# battery_monitor_6803-2_Rev5.net
KiCad netlist of a schematic drawn in EAGLE
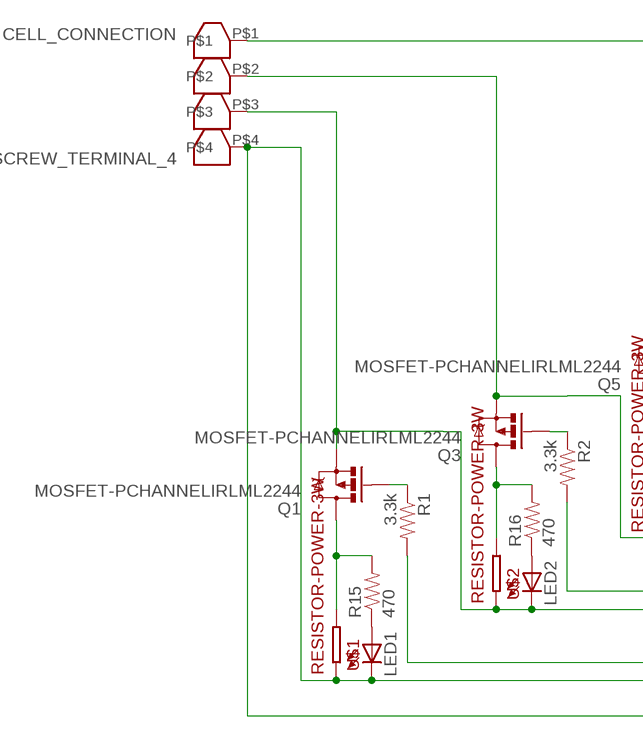
[diagram p0: schematic, sheet 1, part 1 of 2]
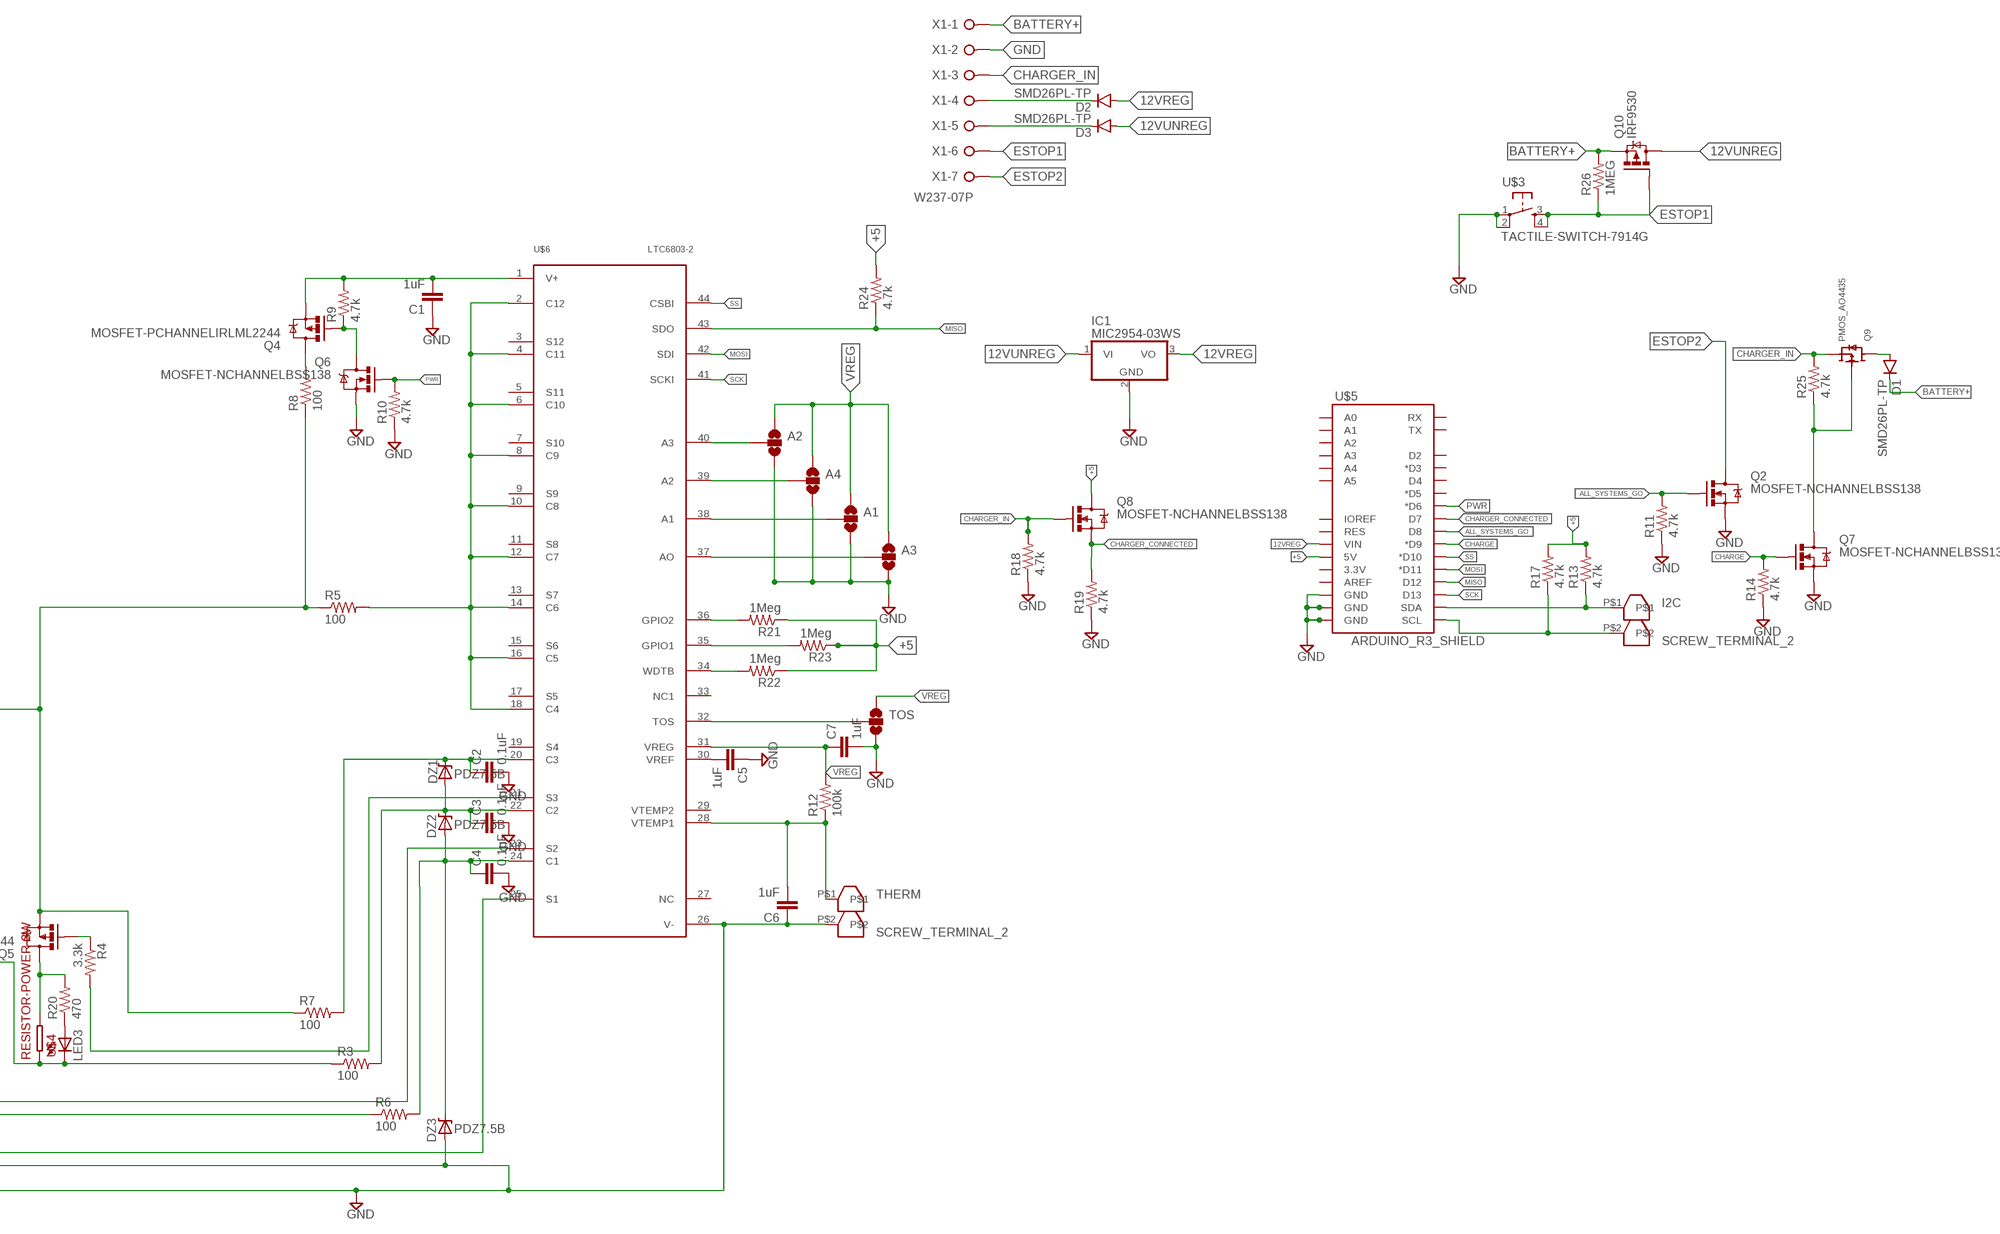
[diagram p1: schematic, sheet 1, part 2 of 2]

(export (version "E")
  (design (tool "Eeschema 10.0.6"))
  (components
    (comp (ref "A1")
      (value "SOLDERJUMPER_2WAYS")
      (footprint "eagle-import:SJ_3")
      (libsource (lib "eagle-import") (part "SOLDERJUMPER_2WAYS"))
    )
    (comp (ref "A2")
      (value "SOLDERJUMPER_2WAYS")
      (footprint "eagle-import:SJ_3")
      (libsource (lib "eagle-import") (part "SOLDERJUMPER_2WAYS"))
    )
    (comp (ref "A3")
      (value "SOLDERJUMPER_2WAYS")
      (footprint "eagle-import:SJ_3")
      (libsource (lib "eagle-import") (part "SOLDERJUMPER_2WAYS"))
    )
    (comp (ref "A4")
      (value "SOLDERJUMPER_2WAYS")
      (footprint "eagle-import:SJ_3")
      (libsource (lib "eagle-import") (part "SOLDERJUMPER_2WAYS"))
    )
    (comp (ref "C1")
      (value "1uF")
      (footprint "eagle-import:0603-CAP")
      (fields (field (name "MPN") "C0603X5R0J105M030BC") (field (name "PROD_ID") "CAP-08390"))
      (libsource (lib "eagle-import") (part "0.1UF-100V-10%(0603)"))
    )
    (comp (ref "C2")
      (value "0.1uF")
      (footprint "eagle-import:0603-CAP")
      (fields (field (name "MF") "AVX CORPORATION") (field (name "MPN") "0603YG104ZAT2A"))
      (libsource (lib "eagle-import") (part "0.1UF-100V-10%(0603)"))
    )
    (comp (ref "C3")
      (value "0.1uF")
      (footprint "eagle-import:0603-CAP")
      (fields (field (name "MF") "AVX CORPORATION") (field (name "MPN") "0603YG104ZAT2A"))
      (libsource (lib "eagle-import") (part "0.1UF-100V-10%(0603)"))
    )
    (comp (ref "C4")
      (value "0.1uF")
      (footprint "eagle-import:0603-CAP")
      (fields (field (name "MF") "AVX CORPORATION") (field (name "MPN") "0603YG104ZAT2A"))
      (libsource (lib "eagle-import") (part "0.1UF-100V-10%(0603)"))
    )
    (comp (ref "C5")
      (value "1uF")
      (footprint "eagle-import:0603-CAP")
      (fields (field (name "MPN") "C0603X5R0J105M030BC") (field (name "PROD_ID") "CAP-08390"))
      (libsource (lib "eagle-import") (part "0.1UF-100V-10%(0603)"))
    )
    (comp (ref "C6")
      (value "1uF")
      (footprint "eagle-import:0603-CAP")
      (fields (field (name "MPN") "C0603X5R0J105M030BC") (field (name "PROD_ID") "CAP-08390"))
      (libsource (lib "eagle-import") (part "0.1UF-100V-10%(0603)"))
    )
    (comp (ref "C7")
      (value "1uF")
      (footprint "eagle-import:0603-CAP")
      (fields (field (name "MPN") "C0603X5R0J105M030BC") (field (name "PROD_ID") "CAP-08390"))
      (libsource (lib "eagle-import") (part "0.1UF-100V-10%(0603)"))
    )
    (comp (ref "CELL_CONNECTION")
      (value "SCREW_TERMINAL_4")
      (footprint "eagle-import:SCREW_TERMINAL_4")
      (fields (field (name "MF") "TYCO ELECTRONICS") (field (name "MPN") "282834-4"))
      (libsource (lib "eagle-import") (part "SCREW_TERMINAL_4"))
    )
    (comp (ref "D1")
      (value "SMD26PL-TP")
      (footprint "eagle-import:SOD-123")
      (libsource (lib "eagle-import") (part "DIODESOD123"))
    )
    (comp (ref "D2")
      (value "SMD26PL-TP")
      (footprint "eagle-import:SOD-123")
      (libsource (lib "eagle-import") (part "DIODESOD123"))
    )
    (comp (ref "D3")
      (value "SMD26PL-TP")
      (footprint "eagle-import:SOD-123")
      (libsource (lib "eagle-import") (part "DIODESOD123"))
    )
    (comp (ref "DZ1")
      (value "PDZ7.5B")
      (footprint "eagle-import:SOD-323@1")
      (fields (field (name "MPN") "PDZ7.5B,115"))
      (libsource (lib "eagle-import") (part "DIODE-ZENER-BZT52"))
    )
    (comp (ref "DZ2")
      (value "PDZ7.5B")
      (footprint "eagle-import:SOD-323@1")
      (fields (field (name "MPN") "PDZ7.5B,115"))
      (libsource (lib "eagle-import") (part "DIODE-ZENER-BZT52"))
    )
    (comp (ref "DZ3")
      (value "PDZ7.5B")
      (footprint "eagle-import:SOD-323@1")
      (fields (field (name "MPN") "PDZ7.5B,115"))
      (libsource (lib "eagle-import") (part "DIODE-ZENER-BZT52"))
    )
    (comp (ref "I2C")
      (value "SCREW_TERMINAL_2")
      (footprint "eagle-import:SCREW_TERMINAL_2")
      (fields (field (name "MF") "TYCO ELECTRONICS") (field (name "MPN") "282834-2"))
      (libsource (lib "eagle-import") (part "SCREW_TERMINAL_2"))
    )
    (comp (ref "IC1")
      (value "MIC2954-03WS")
      (footprint "eagle-import:SOT223")
      (libsource (lib "eagle-import") (part "MCP1703DB"))
    )
    (comp (ref "LED1")
      (value "LED0603")
      (footprint "eagle-import:LED-0603")
      (fields (field (name "MPN") "150060RS75000"))
      (libsource (lib "eagle-import") (part "LED0603"))
    )
    (comp (ref "LED2")
      (value "LED0603")
      (footprint "eagle-import:LED-0603")
      (fields (field (name "MPN") "150060RS75000"))
      (libsource (lib "eagle-import") (part "LED0603"))
    )
    (comp (ref "LED3")
      (value "LED0603")
      (footprint "eagle-import:LED-0603")
      (fields (field (name "MPN") "150060RS75000"))
      (libsource (lib "eagle-import") (part "LED0603"))
    )
    (comp (ref "Q1")
      (value "MOSFET-PCHANNELIRLML2244")
      (footprint "eagle-import:SOT23-3@1")
      (fields (field (name "MPN") "SI2369DS-T1-GE3"))
      (libsource (lib "eagle-import") (part "MOSFET-PCHANNELIRLML2244"))
    )
    (comp (ref "Q2")
      (value "MOSFET-NCHANNELBSS138")
      (footprint "eagle-import:SOT23")
      (fields (field (name "MPN") "IRLML0030TRPBF"))
      (libsource (lib "eagle-import") (part "MOSFET-NCHANNELBSS138"))
    )
    (comp (ref "Q3")
      (value "MOSFET-PCHANNELIRLML2244")
      (footprint "eagle-import:SOT23-3@1")
      (fields (field (name "MPN") "SI2369DS-T1-GE3"))
      (libsource (lib "eagle-import") (part "MOSFET-PCHANNELIRLML2244"))
    )
    (comp (ref "Q4")
      (value "MOSFET-PCHANNELIRLML2244")
      (footprint "eagle-import:SOT23-3@1")
      (fields (field (name "MPN") "SI2369DS-T1-GE3"))
      (libsource (lib "eagle-import") (part "MOSFET-PCHANNELIRLML2244"))
    )
    (comp (ref "Q5")
      (value "MOSFET-PCHANNELIRLML2244")
      (footprint "eagle-import:SOT23-3@1")
      (fields (field (name "MPN") "SI2369DS-T1-GE3"))
      (libsource (lib "eagle-import") (part "MOSFET-PCHANNELIRLML2244"))
    )
    (comp (ref "Q6")
      (value "MOSFET-NCHANNELBSS138")
      (footprint "eagle-import:SOT23")
      (fields (field (name "MPN") "IRLML0030TRPBF"))
      (libsource (lib "eagle-import") (part "MOSFET-NCHANNELBSS138"))
    )
    (comp (ref "Q7")
      (value "MOSFET-NCHANNELBSS138")
      (footprint "eagle-import:SOT23")
      (fields (field (name "MPN") "IRLML0030TRPBF"))
      (libsource (lib "eagle-import") (part "MOSFET-NCHANNELBSS138"))
    )
    (comp (ref "Q8")
      (value "MOSFET-NCHANNELBSS138")
      (footprint "eagle-import:SOT23")
      (fields (field (name "MPN") "IRLML0030TRPBF") (field (name "PROD_ID") "TRANS-00830"))
      (libsource (lib "eagle-import") (part "MOSFET-NCHANNELBSS138"))
    )
    (comp (ref "Q9")
      (value "PMOS_AO4435")
      (footprint "eagle-import:SOIC8")
      (fields (field (name "MPN") "SI9407BDY-T1-GE3"))
      (libsource (lib "eagle-import") (part "PMOS_AO4435"))
    )
    (comp (ref "Q10")
      (value "IRF9530")
      (footprint "eagle-import:TO220BV")
      (fields (field (name "MPN") "NTE2383"))
      (libsource (lib "eagle-import") (part "IRF9530"))
    )
    (comp (ref "R1")
      (value "3.3k")
      (footprint "eagle-import:0603-RES")
      (fields (field (name "MF") "VISHAY/DALE") (field (name "MPN") "CRCW06033K00FKEA"))
      (libsource (lib "eagle-import") (part "3.3KOHM1/10W1%(0603)"))
    )
    (comp (ref "R2")
      (value "3.3k")
      (footprint "eagle-import:0603-RES")
      (fields (field (name "MF") "VISHAY/DALE") (field (name "MPN") "CRCW06033K00FKEA"))
      (libsource (lib "eagle-import") (part "3.3KOHM1/10W1%(0603)"))
    )
    (comp (ref "R3")
      (value "100")
      (footprint "eagle-import:0603-RES")
      (fields (field (name "MPN") "ERJ-1GNF1000C"))
      (libsource (lib "eagle-import") (part "3.3KOHM1/10W1%(0603)"))
    )
    (comp (ref "R4")
      (value "3.3k")
      (footprint "eagle-import:0603-RES")
      (fields (field (name "MF") "VISHAY/DALE") (field (name "MPN") "CRCW06033K00FKEA"))
      (libsource (lib "eagle-import") (part "3.3KOHM1/10W1%(0603)"))
    )
    (comp (ref "R5")
      (value "100")
      (footprint "eagle-import:0603-RES")
      (fields (field (name "MPN") "ERJ-1GNF1000C"))
      (libsource (lib "eagle-import") (part "3.3KOHM1/10W1%(0603)"))
    )
    (comp (ref "R6")
      (value "100")
      (footprint "eagle-import:0603-RES")
      (fields (field (name "MPN") "ERJ-1GNF1000C"))
      (libsource (lib "eagle-import") (part "3.3KOHM1/10W1%(0603)"))
    )
    (comp (ref "R7")
      (value "100")
      (footprint "eagle-import:0603-RES")
      (fields (field (name "MPN") "ERJ-1GNF1000C"))
      (libsource (lib "eagle-import") (part "3.3KOHM1/10W1%(0603)"))
    )
    (comp (ref "R8")
      (value "100")
      (footprint "eagle-import:0603-RES")
      (fields (field (name "MPN") "ERJ-1GNF1000C"))
      (libsource (lib "eagle-import") (part "3.3KOHM1/10W1%(0603)"))
    )
    (comp (ref "R9")
      (value "4.7k")
      (footprint "eagle-import:0603-RES")
      (fields (field (name "MF") "VISHAY/DALE") (field (name "MPN") "CRCW06034K70FKEA"))
      (libsource (lib "eagle-import") (part "3.3KOHM1/10W1%(0603)"))
    )
    (comp (ref "R10")
      (value "4.7k")
      (footprint "eagle-import:0603-RES")
      (fields (field (name "MF") "VISHAY/DALE") (field (name "MPN") "CRCW06034K70FKEA"))
      (libsource (lib "eagle-import") (part "3.3KOHM1/10W1%(0603)"))
    )
    (comp (ref "R11")
      (value "4.7k")
      (footprint "eagle-import:0603-RES")
      (fields (field (name "MF") "VISHAY/DALE") (field (name "MPN") "CRCW06034K70FKEA"))
      (libsource (lib "eagle-import") (part "3.3KOHM1/10W1%(0603)"))
    )
    (comp (ref "R12")
      (value "100k")
      (footprint "eagle-import:0603-RES")
      (fields (field (name "MF") "FARNELL") (field (name "MPN") "MC0063W06035100K"))
      (libsource (lib "eagle-import") (part "3.3KOHM1/10W1%(0603)"))
    )
    (comp (ref "R13")
      (value "4.7k")
      (footprint "eagle-import:0603-RES")
      (fields (field (name "MF") "VISHAY/DALE") (field (name "MPN") "CRCW06034K70FKEA"))
      (libsource (lib "eagle-import") (part "3.3KOHM1/10W1%(0603)"))
    )
    (comp (ref "R14")
      (value "4.7k")
      (footprint "eagle-import:0603-RES")
      (fields (field (name "MF") "VISHAY/DALE") (field (name "MPN") "CRCW06034K70FKEA"))
      (libsource (lib "eagle-import") (part "3.3KOHM1/10W1%(0603)"))
    )
    (comp (ref "R15")
      (value "470")
      (footprint "eagle-import:0603-RES")
      (fields (field (name "MPN") "ERJ-P03F4700V") (field (name "PROD_ID") "RES-07851"))
      (libsource (lib "eagle-import") (part "3.3KOHM1/10W1%(0603)"))
    )
    (comp (ref "R16")
      (value "470")
      (footprint "eagle-import:0603-RES")
      (fields (field (name "MPN") "ERJ-P03F4700V") (field (name "PROD_ID") "RES-07851"))
      (libsource (lib "eagle-import") (part "3.3KOHM1/10W1%(0603)"))
    )
    (comp (ref "R17")
      (value "4.7k")
      (footprint "eagle-import:0603-RES")
      (fields (field (name "MF") "VISHAY/DALE") (field (name "MPN") "CRCW06034K70FKEA"))
      (libsource (lib "eagle-import") (part "3.3KOHM1/10W1%(0603)"))
    )
    (comp (ref "R18")
      (value "4.7k")
      (footprint "eagle-import:0603-RES")
      (fields
        (field (name "MF") "VISHAY/DALE")
        (field (name "MPN") "CRCW06034K70FKEA")
        (field (name "PROD_ID") "RES-07851")
      )
      (libsource (lib "eagle-import") (part "3.3KOHM1/10W1%(0603)"))
    )
    (comp (ref "R19")
      (value "4.7k")
      (footprint "eagle-import:0603-RES")
      (fields
        (field (name "MF") "VISHAY/DALE")
        (field (name "MPN") "CRCW06034K70FKEA")
        (field (name "PROD_ID") "RES-07851")
      )
      (libsource (lib "eagle-import") (part "3.3KOHM1/10W1%(0603)"))
    )
    (comp (ref "R20")
      (value "470")
      (footprint "eagle-import:0603-RES")
      (fields (field (name "MPN") "ERJ-P03F4700V") (field (name "PROD_ID") "RES-07851"))
      (libsource (lib "eagle-import") (part "3.3KOHM1/10W1%(0603)"))
    )
    (comp (ref "R21")
      (value "1Meg")
      (footprint "eagle-import:0603-RES")
      (fields (field (name "MPN") "ERJ-3EKF1004V") (field (name "PROD_ID") "RES-07851"))
      (libsource (lib "eagle-import") (part "3.3KOHM1/10W1%(0603)"))
    )
    (comp (ref "R22")
      (value "1Meg")
      (footprint "eagle-import:0603-RES")
      (fields (field (name "MPN") "ERJ-3EKF1004V") (field (name "PROD_ID") "RES-07851"))
      (libsource (lib "eagle-import") (part "3.3KOHM1/10W1%(0603)"))
    )
    (comp (ref "R23")
      (value "1Meg")
      (footprint "eagle-import:0603-RES")
      (fields (field (name "MPN") "ERJ-3EKF1004V") (field (name "PROD_ID") "RES-07851"))
      (libsource (lib "eagle-import") (part "3.3KOHM1/10W1%(0603)"))
    )
    (comp (ref "R24")
      (value "4.7k")
      (footprint "eagle-import:0603-RES")
      (fields
        (field (name "MF") "VISHAY/DALE")
        (field (name "MPN") "CRCW06034K70FKEA")
        (field (name "PROD_ID") "RES-07851")
      )
      (libsource (lib "eagle-import") (part "3.3KOHM1/10W1%(0603)"))
    )
    (comp (ref "R25")
      (value "4.7k")
      (footprint "eagle-import:0603-RES")
      (fields
        (field (name "MF") "VISHAY/DALE")
        (field (name "MPN") "CRCW06034K70FKEA")
        (field (name "PROD_ID") "RES-07851")
      )
      (libsource (lib "eagle-import") (part "3.3KOHM1/10W1%(0603)"))
    )
    (comp (ref "R26")
      (value "1MEG")
      (footprint "eagle-import:0603-RES")
      (fields (field (name "MPN") "ERJ-3EKF1004V"))
      (libsource (lib "eagle-import") (part "3.3KOHM1/10W1%(0603)"))
    )
    (comp (ref "THERM")
      (value "SCREW_TERMINAL_2")
      (footprint "eagle-import:SCREW_TERMINAL_2")
      (fields (field (name "MF") "TYCO ELECTRONICS") (field (name "MPN") "282834-2"))
      (libsource (lib "eagle-import") (part "SCREW_TERMINAL_2"))
    )
    (comp (ref "TOS")
      (value "SOLDERJUMPER_2WAYS")
      (footprint "eagle-import:SJ_3")
      (libsource (lib "eagle-import") (part "SOLDERJUMPER_2WAYS"))
    )
    (comp (ref "U$1")
      (value "RESISTOR-POWER-3W")
      (footprint "eagle-import:RESISTOR-3W")
      (fields (field (name "MPN") "ERG-3SJ200"))
      (libsource (lib "eagle-import") (part "RESISTOR-POWER-3W"))
    )
    (comp (ref "U$2")
      (value "RESISTOR-POWER-3W")
      (footprint "eagle-import:RESISTOR-3W")
      (fields (field (name "MPN") "ERG-3SJ200"))
      (libsource (lib "eagle-import") (part "RESISTOR-POWER-3W"))
    )
    (comp (ref "U$3")
      (value "TACTILE-SWITCH-7914G")
      (footprint "eagle-import:7914G")
      (fields (field (name "MF") "BOURNS, INC.") (field (name "MPN") "7914G-1-000E"))
      (libsource (lib "eagle-import") (part "TACTILE-SWITCH-7914G"))
    )
    (comp (ref "U$4")
      (value "RESISTOR-POWER-3W")
      (footprint "eagle-import:RESISTOR-3W")
      (fields (field (name "MPN") "ERG-3SJ200"))
      (libsource (lib "eagle-import") (part "RESISTOR-POWER-3W"))
    )
    (comp (ref "U$5")
      (value "ARDUINO_R3_SHIELD")
      (footprint "eagle-import:UNO_R3_SHIELD")
      (libsource (lib "eagle-import") (part "ARDUINO_R3_SHIELD"))
    )
    (comp (ref "U$6")
      (value "LTC6803-2")
      (footprint "eagle-import:FSOP-44")
      (libsource (lib "eagle-import") (part "LTC6803-2"))
    )
    (comp (ref "X1")
      (value "W237-07P")
      (footprint "eagle-import:W237-7P")
      (libsource (lib "eagle-import") (part "W237-07P"))
    )
  )
  (nets
    (net (code "1") (name "+5") (class "Default")
      (node (ref "Q8") (pin "3") (pinfunction "D_3") (pintype "passive"))
      (node (ref "R13") (pin "2") (pinfunction "2_2") (pintype "passive"))
      (node (ref "R17") (pin "2") (pinfunction "2_2") (pintype "passive"))
      (node (ref "R21") (pin "1") (pinfunction "1_1") (pintype "passive"))
      (node (ref "R22") (pin "1") (pinfunction "1_1") (pintype "passive"))
      (node (ref "R23") (pin "1") (pinfunction "1_1") (pintype "passive"))
      (node (ref "R24") (pin "2") (pinfunction "2_2") (pintype "passive"))
      (node (ref "U$5") (pin "5V") (pinfunction "5V_5V") (pintype "bidirectional"))
    )
    (net (code "2") (name "12VREG") (class "Default")
      (node (ref "D2") (pin "A") (pinfunction "A_A") (pintype "passive"))
      (node (ref "IC1") (pin "3") (pinfunction "VO_3") (pintype "passive"))
      (node (ref "U$5") (pin "VIN") (pinfunction "VIN_VIN") (pintype "bidirectional"))
    )
    (net (code "3") (name "12VUNREG") (class "Default")
      (node (ref "D3") (pin "A") (pinfunction "A_A") (pintype "passive"))
      (node (ref "IC1") (pin "1") (pinfunction "VI_1") (pintype "input"))
      (node (ref "Q10") (pin "D") (pinfunction "D_D") (pintype "passive"))
    )
    (net (code "4") (name "ALL_SYSTEMS_GO") (class "Default")
      (node (ref "Q2") (pin "1") (pinfunction "G_1") (pintype "passive"))
      (node (ref "R11") (pin "2") (pinfunction "2_2") (pintype "passive"))
      (node (ref "U$5") (pin "D8") (pinfunction "D8_D8") (pintype "bidirectional"))
    )
    (net (code "5") (name "BATTERY+") (class "Default")
      (node (ref "D1") (pin "C") (pinfunction "C_C") (pintype "passive"))
      (node (ref "Q10") (pin "S") (pinfunction "S_S") (pintype "passive"))
      (node (ref "R26") (pin "2") (pinfunction "2_2") (pintype "passive"))
      (node (ref "X1") (pin "1") (pinfunction "KL_1") (pintype "passive"))
    )
    (net (code "6") (name "CHARGE") (class "Default")
      (node (ref "Q7") (pin "1") (pinfunction "G_1") (pintype "passive"))
      (node (ref "R14") (pin "2") (pinfunction "2_2") (pintype "passive"))
      (node (ref "U$5") (pin "D9") (pinfunction "*D9_D9") (pintype "bidirectional"))
    )
    (net (code "7") (name "CHARGER_CONNECTED") (class "Default")
      (node (ref "Q8") (pin "2") (pinfunction "S_2") (pintype "passive"))
      (node (ref "R19") (pin "2") (pinfunction "2_2") (pintype "passive"))
      (node (ref "U$5") (pin "D7") (pinfunction "D7_D7") (pintype "bidirectional"))
    )
    (net (code "8") (name "CHARGER_IN") (class "Default")
      (node (ref "Q8") (pin "1") (pinfunction "G_1") (pintype "passive"))
      (node (ref "Q9") (pin "1") (pinfunction "SOURCE_1") (pintype "bidirectional"))
      (node (ref "Q9") (pin "2") (pinfunction "SOURCE_2") (pintype "bidirectional"))
      (node (ref "Q9") (pin "3") (pinfunction "SOURCE_3") (pintype "bidirectional"))
      (node (ref "R18") (pin "2") (pinfunction "2_2") (pintype "passive"))
      (node (ref "R25") (pin "2") (pinfunction "2_2") (pintype "passive"))
      (node (ref "X1") (pin "3") (pinfunction "KL_3") (pintype "passive"))
    )
    (net (code "9") (name "ESTOP1") (class "Default")
      (node (ref "Q10") (pin "G") (pinfunction "G_G") (pintype "passive"))
      (node (ref "R26") (pin "1") (pinfunction "1_1") (pintype "passive"))
      (node (ref "U$3") (pin "3") (pinfunction "3_3") (pintype "passive"))
      (node (ref "U$3") (pin "4") (pinfunction "4_4") (pintype "passive"))
      (node (ref "X1") (pin "6") (pinfunction "KL_6") (pintype "passive"))
    )
    (net (code "10") (name "ESTOP2") (class "Default")
      (node (ref "Q2") (pin "3") (pinfunction "D_3") (pintype "passive"))
      (node (ref "X1") (pin "7") (pinfunction "KL_7") (pintype "passive"))
    )
    (net (code "11") (name "GND") (class "Default")
      (node (ref "A1") (pin "3") (pinfunction "3_3") (pintype "passive"))
      (node (ref "A2") (pin "3") (pinfunction "3_3") (pintype "passive"))
      (node (ref "A3") (pin "3") (pinfunction "3_3") (pintype "passive"))
      (node (ref "A4") (pin "3") (pinfunction "3_3") (pintype "passive"))
      (node (ref "C1") (pin "1") (pinfunction "1_1") (pintype "passive"))
      (node (ref "C2") (pin "2") (pinfunction "2_2") (pintype "passive"))
      (node (ref "C3") (pin "2") (pinfunction "2_2") (pintype "passive"))
      (node (ref "C4") (pin "2") (pinfunction "2_2") (pintype "passive"))
      (node (ref "C5") (pin "1") (pinfunction "1_1") (pintype "passive"))
      (node (ref "C6") (pin "1") (pinfunction "1_1") (pintype "passive"))
      (node (ref "C7") (pin "2") (pinfunction "2_2") (pintype "passive"))
      (node (ref "CELL_CONNECTION") (pin "P$4") (pinfunction "P$4_P$4") (pintype "bidirectional"))
      (node (ref "DZ3") (pin "2") (pinfunction "A_2") (pintype "passive"))
      (node (ref "IC1") (pin "2") (pinfunction "GND_2") (pintype "passive"))
      (node (ref "LED1") (pin "C") (pinfunction "C_C") (pintype "passive"))
      (node (ref "Q2") (pin "2") (pinfunction "S_2") (pintype "passive"))
      (node (ref "Q6") (pin "2") (pinfunction "S_2") (pintype "passive"))
      (node (ref "Q7") (pin "2") (pinfunction "S_2") (pintype "passive"))
      (node (ref "R10") (pin "1") (pinfunction "1_1") (pintype "passive"))
      (node (ref "R11") (pin "1") (pinfunction "1_1") (pintype "passive"))
      (node (ref "R14") (pin "1") (pinfunction "1_1") (pintype "passive"))
      (node (ref "R18") (pin "1") (pinfunction "1_1") (pintype "passive"))
      (node (ref "R19") (pin "1") (pinfunction "1_1") (pintype "passive"))
      (node (ref "THERM") (pin "P$2") (pinfunction "P$2_P$2") (pintype "bidirectional"))
      (node (ref "TOS") (pin "3") (pinfunction "3_3") (pintype "passive"))
      (node (ref "U$1") (pin "P$2") (pinfunction "P$2_P$2") (pintype "bidirectional"))
      (node (ref "U$3") (pin "1") (pinfunction "1_1") (pintype "passive"))
      (node (ref "U$3") (pin "2") (pinfunction "2_2") (pintype "passive"))
      (node (ref "U$5") (pin "GND@0") (pinfunction "GND_GND@0") (pintype "bidirectional"))
      (node (ref "U$5") (pin "GND@1") (pinfunction "GND_GND@1") (pintype "bidirectional"))
      (node (ref "U$5") (pin "GND@2") (pinfunction "GND_GND@2") (pintype "bidirectional"))
      (node (ref "U$6") (pin "26") (pinfunction "V-_26") (pintype "bidirectional"))
      (node (ref "X1") (pin "2") (pinfunction "KL_2") (pintype "passive"))
    )
    (net (code "12") (name "MISO") (class "Default")
      (node (ref "R24") (pin "1") (pinfunction "1_1") (pintype "passive"))
      (node (ref "U$5") (pin "D12") (pinfunction "D12_D12") (pintype "bidirectional"))
      (node (ref "U$6") (pin "43") (pinfunction "SDO_43") (pintype "bidirectional"))
    )
    (net (code "13") (name "MOSI") (class "Default")
      (node (ref "U$5") (pin "D11") (pinfunction "*D11_D11") (pintype "bidirectional"))
      (node (ref "U$6") (pin "42") (pinfunction "SDI_42") (pintype "bidirectional"))
    )
    (net (code "14") (name "Net-(D1-PadA)") (class "Default")
      (node (ref "D1") (pin "A") (pinfunction "A_A") (pintype "passive"))
      (node (ref "Q9") (pin "5") (pinfunction "DRAIN_5") (pintype "bidirectional"))
      (node (ref "Q9") (pin "6") (pinfunction "DRAIN_6") (pintype "bidirectional"))
      (node (ref "Q9") (pin "7") (pinfunction "DRAIN_7") (pintype "bidirectional"))
      (node (ref "Q9") (pin "8") (pinfunction "DRAIN_8") (pintype "bidirectional"))
    )
    (net (code "15") (name "Net-(DZ1-A)") (class "Default")
      (node (ref "C3") (pin "1") (pinfunction "1_1") (pintype "passive"))
      (node (ref "DZ1") (pin "2") (pinfunction "A_2") (pintype "passive"))
      (node (ref "DZ2") (pin "1") (pinfunction "C_1") (pintype "passive"))
      (node (ref "R3") (pin "2") (pinfunction "2_2") (pintype "passive"))
      (node (ref "U$6") (pin "22") (pinfunction "C2_22") (pintype "bidirectional"))
    )
    (net (code "16") (name "Net-(DZ1-C)") (class "Default")
      (node (ref "C2") (pin "1") (pinfunction "1_1") (pintype "passive"))
      (node (ref "DZ1") (pin "1") (pinfunction "C_1") (pintype "passive"))
      (node (ref "R7") (pin "2") (pinfunction "2_2") (pintype "passive"))
      (node (ref "U$6") (pin "20") (pinfunction "C3_20") (pintype "bidirectional"))
    )
    (net (code "17") (name "Net-(DZ2-A)") (class "Default")
      (node (ref "C4") (pin "1") (pinfunction "1_1") (pintype "passive"))
      (node (ref "DZ2") (pin "2") (pinfunction "A_2") (pintype "passive"))
      (node (ref "DZ3") (pin "1") (pinfunction "C_1") (pintype "passive"))
      (node (ref "R6") (pin "2") (pinfunction "2_2") (pintype "passive"))
      (node (ref "U$6") (pin "24") (pinfunction "C1_24") (pintype "bidirectional"))
    )
    (net (code "18") (name "Net-(I2C-PadP$1)") (class "Default")
      (node (ref "I2C") (pin "P$1") (pinfunction "P$1_P$1") (pintype "bidirectional"))
      (node (ref "R13") (pin "1") (pinfunction "1_1") (pintype "passive"))
      (node (ref "U$5") (pin "SDA") (pinfunction "SDA_SDA") (pintype "bidirectional"))
    )
    (net (code "19") (name "Net-(I2C-PadP$2)") (class "Default")
      (node (ref "I2C") (pin "P$2") (pinfunction "P$2_P$2") (pintype "bidirectional"))
      (node (ref "R17") (pin "1") (pinfunction "1_1") (pintype "passive"))
      (node (ref "U$5") (pin "SCL") (pinfunction "SCL_SCL") (pintype "bidirectional"))
    )
    (net (code "20") (name "Net-(LED1-PadA)") (class "Default")
      (node (ref "LED1") (pin "A") (pinfunction "A_A") (pintype "passive"))
      (node (ref "R15") (pin "1") (pinfunction "1_1") (pintype "passive"))
    )
    (net (code "21") (name "Net-(LED2-PadA)") (class "Default")
      (node (ref "LED2") (pin "A") (pinfunction "A_A") (pintype "passive"))
      (node (ref "R16") (pin "1") (pinfunction "1_1") (pintype "passive"))
    )
    (net (code "22") (name "Net-(LED3-PadA)") (class "Default")
      (node (ref "LED3") (pin "A") (pinfunction "A_A") (pintype "passive"))
      (node (ref "R20") (pin "1") (pinfunction "1_1") (pintype "passive"))
    )
    (net (code "23") (name "Net-(Q1-D)") (class "Default")
      (node (ref "Q1") (pin "3") (pinfunction "D_3") (pintype "passive"))
      (node (ref "R15") (pin "2") (pinfunction "2_2") (pintype "passive"))
      (node (ref "U$1") (pin "P$1") (pinfunction "P$1_P$1") (pintype "bidirectional"))
    )
    (net (code "24") (name "Net-(Q1-G)") (class "Default")
      (node (ref "Q1") (pin "1") (pinfunction "G_1") (pintype "passive"))
      (node (ref "R1") (pin "1") (pinfunction "1_1") (pintype "passive"))
    )
    (net (code "25") (name "Net-(Q1-S)") (class "Default")
      (node (ref "CELL_CONNECTION") (pin "P$3") (pinfunction "P$3_P$3") (pintype "bidirectional"))
      (node (ref "LED2") (pin "C") (pinfunction "C_C") (pintype "passive"))
      (node (ref "Q1") (pin "2") (pinfunction "S_2") (pintype "passive"))
      (node (ref "R6") (pin "1") (pinfunction "1_1") (pintype "passive"))
      (node (ref "U$2") (pin "P$2") (pinfunction "P$2_P$2") (pintype "bidirectional"))
    )
    (net (code "26") (name "Net-(Q3-D)") (class "Default")
      (node (ref "Q3") (pin "3") (pinfunction "D_3") (pintype "passive"))
      (node (ref "R16") (pin "2") (pinfunction "2_2") (pintype "passive"))
      (node (ref "U$2") (pin "P$1") (pinfunction "P$1_P$1") (pintype "bidirectional"))
    )
    (net (code "27") (name "Net-(Q3-G)") (class "Default")
      (node (ref "Q3") (pin "1") (pinfunction "G_1") (pintype "passive"))
      (node (ref "R2") (pin "1") (pinfunction "1_1") (pintype "passive"))
    )
    (net (code "28") (name "Net-(Q3-S)") (class "Default")
      (node (ref "CELL_CONNECTION") (pin "P$2") (pinfunction "P$2_P$2") (pintype "bidirectional"))
      (node (ref "LED3") (pin "C") (pinfunction "C_C") (pintype "passive"))
      (node (ref "Q3") (pin "2") (pinfunction "S_2") (pintype "passive"))
      (node (ref "R3") (pin "1") (pinfunction "1_1") (pintype "passive"))
      (node (ref "U$4") (pin "P$2") (pinfunction "P$2_P$2") (pintype "bidirectional"))
    )
    (net (code "29") (name "Net-(Q4-D)") (class "Default")
      (node (ref "Q4") (pin "3") (pinfunction "D_3") (pintype "passive"))
      (node (ref "R8") (pin "2") (pinfunction "2_2") (pintype "passive"))
    )
    (net (code "30") (name "Net-(Q4-G)") (class "Default")
      (node (ref "Q4") (pin "1") (pinfunction "G_1") (pintype "passive"))
      (node (ref "Q6") (pin "3") (pinfunction "D_3") (pintype "passive"))
      (node (ref "R9") (pin "1") (pinfunction "1_1") (pintype "passive"))
    )
    (net (code "31") (name "Net-(Q4-S)") (class "Default")
      (node (ref "C1") (pin "2") (pinfunction "2_2") (pintype "passive"))
      (node (ref "Q4") (pin "2") (pinfunction "S_2") (pintype "passive"))
      (node (ref "R9") (pin "2") (pinfunction "2_2") (pintype "passive"))
      (node (ref "U$6") (pin "1") (pinfunction "V+_1") (pintype "bidirectional"))
    )
    (net (code "32") (name "Net-(Q5-D)") (class "Default")
      (node (ref "Q5") (pin "3") (pinfunction "D_3") (pintype "passive"))
      (node (ref "R20") (pin "2") (pinfunction "2_2") (pintype "passive"))
      (node (ref "U$4") (pin "P$1") (pinfunction "P$1_P$1") (pintype "bidirectional"))
    )
    (net (code "33") (name "Net-(Q5-G)") (class "Default")
      (node (ref "Q5") (pin "1") (pinfunction "G_1") (pintype "passive"))
      (node (ref "R4") (pin "1") (pinfunction "1_1") (pintype "passive"))
    )
    (net (code "34") (name "Net-(Q5-S)") (class "Default")
      (node (ref "CELL_CONNECTION") (pin "P$1") (pinfunction "P$1_P$1") (pintype "bidirectional"))
      (node (ref "Q5") (pin "2") (pinfunction "S_2") (pintype "passive"))
      (node (ref "R5") (pin "1") (pinfunction "1_1") (pintype "passive"))
      (node (ref "R7") (pin "1") (pinfunction "1_1") (pintype "passive"))
      (node (ref "R8") (pin "1") (pinfunction "1_1") (pintype "passive"))
    )
    (net (code "35") (name "Net-(Q7-D)") (class "Default")
      (node (ref "Q7") (pin "3") (pinfunction "D_3") (pintype "passive"))
      (node (ref "Q9") (pin "4") (pinfunction "GATE_4") (pintype "bidirectional"))
      (node (ref "R25") (pin "1") (pinfunction "1_1") (pintype "passive"))
    )
    (net (code "36") (name "Net-(U$6-A1)") (class "Default")
      (node (ref "A1") (pin "2") (pinfunction "2_2") (pintype "passive"))
      (node (ref "U$6") (pin "38") (pinfunction "A1_38") (pintype "bidirectional"))
    )
    (net (code "37") (name "Net-(U$6-A2)") (class "Default")
      (node (ref "A4") (pin "2") (pinfunction "2_2") (pintype "passive"))
      (node (ref "U$6") (pin "39") (pinfunction "A2_39") (pintype "bidirectional"))
    )
    (net (code "38") (name "Net-(U$6-A3)") (class "Default")
      (node (ref "A2") (pin "2") (pinfunction "2_2") (pintype "passive"))
      (node (ref "U$6") (pin "40") (pinfunction "A3_40") (pintype "bidirectional"))
    )
    (net (code "39") (name "Net-(U$6-AO)") (class "Default")
      (node (ref "A3") (pin "2") (pinfunction "2_2") (pintype "passive"))
      (node (ref "U$6") (pin "37") (pinfunction "AO_37") (pintype "bidirectional"))
    )
    (net (code "40") (name "Net-(U$6-C10)") (class "Default")
      (node (ref "R5") (pin "2") (pinfunction "2_2") (pintype "passive"))
      (node (ref "U$6") (pin "10") (pinfunction "C8_10") (pintype "bidirectional"))
      (node (ref "U$6") (pin "12") (pinfunction "C7_12") (pintype "bidirectional"))
      (node (ref "U$6") (pin "14") (pinfunction "C6_14") (pintype "bidirectional"))
      (node (ref "U$6") (pin "16") (pinfunction "C5_16") (pintype "bidirectional"))
      (node (ref "U$6") (pin "18") (pinfunction "C4_18") (pintype "bidirectional"))
      (node (ref "U$6") (pin "2") (pinfunction "C12_2") (pintype "bidirectional"))
      (node (ref "U$6") (pin "4") (pinfunction "C11_4") (pintype "bidirectional"))
      (node (ref "U$6") (pin "6") (pinfunction "C10_6") (pintype "bidirectional"))
      (node (ref "U$6") (pin "8") (pinfunction "C9_8") (pintype "bidirectional"))
    )
    (net (code "41") (name "Net-(U$6-GPIO1)") (class "Default")
      (node (ref "R23") (pin "2") (pinfunction "2_2") (pintype "passive"))
      (node (ref "U$6") (pin "35") (pinfunction "GPIO1_35") (pintype "bidirectional"))
    )
    (net (code "42") (name "Net-(U$6-GPIO2)") (class "Default")
      (node (ref "R21") (pin "2") (pinfunction "2_2") (pintype "passive"))
      (node (ref "U$6") (pin "36") (pinfunction "GPIO2_36") (pintype "bidirectional"))
    )
    (net (code "43") (name "Net-(U$6-S1)") (class "Default")
      (node (ref "R1") (pin "2") (pinfunction "2_2") (pintype "passive"))
      (node (ref "U$6") (pin "25") (pinfunction "S1_25") (pintype "bidirectional"))
    )
    (net (code "44") (name "Net-(U$6-S2)") (class "Default")
      (node (ref "R2") (pin "2") (pinfunction "2_2") (pintype "passive"))
      (node (ref "U$6") (pin "23") (pinfunction "S2_23") (pintype "bidirectional"))
    )
    (net (code "45") (name "Net-(U$6-S3)") (class "Default")
      (node (ref "R4") (pin "2") (pinfunction "2_2") (pintype "passive"))
      (node (ref "U$6") (pin "21") (pinfunction "S3_21") (pintype "bidirectional"))
    )
    (net (code "46") (name "Net-(U$6-TOS)") (class "Default")
      (node (ref "TOS") (pin "2") (pinfunction "2_2") (pintype "passive"))
      (node (ref "U$6") (pin "32") (pinfunction "TOS_32") (pintype "bidirectional"))
    )
    (net (code "47") (name "Net-(U$6-VREF)") (class "Default")
      (node (ref "C5") (pin "2") (pinfunction "2_2") (pintype "passive"))
      (node (ref "U$6") (pin "30") (pinfunction "VREF_30") (pintype "bidirectional"))
    )
    (net (code "48") (name "Net-(U$6-VTEMP1)") (class "Default")
      (node (ref "C6") (pin "2") (pinfunction "2_2") (pintype "passive"))
      (node (ref "R12") (pin "1") (pinfunction "1_1") (pintype "passive"))
      (node (ref "THERM") (pin "P$1") (pinfunction "P$1_P$1") (pintype "bidirectional"))
      (node (ref "U$6") (pin "28") (pinfunction "VTEMP1_28") (pintype "bidirectional"))
    )
    (net (code "49") (name "Net-(U$6-WDTB)") (class "Default")
      (node (ref "R22") (pin "2") (pinfunction "2_2") (pintype "passive"))
      (node (ref "U$6") (pin "34") (pinfunction "WDTB_34") (pintype "bidirectional"))
    )
    (net (code "50") (name "Net-(X1D-KL)") (class "Default")
      (node (ref "D2") (pin "C") (pinfunction "C_C") (pintype "passive"))
      (node (ref "X1") (pin "4") (pinfunction "KL_4") (pintype "passive"))
    )
    (net (code "51") (name "Net-(X1E-KL)") (class "Default")
      (node (ref "D3") (pin "C") (pinfunction "C_C") (pintype "passive"))
      (node (ref "X1") (pin "5") (pinfunction "KL_5") (pintype "passive"))
    )
    (net (code "52") (name "PWR") (class "Default")
      (node (ref "Q6") (pin "1") (pinfunction "G_1") (pintype "passive"))
      (node (ref "R10") (pin "2") (pinfunction "2_2") (pintype "passive"))
      (node (ref "U$5") (pin "D6") (pinfunction "*D6_D6") (pintype "bidirectional"))
    )
    (net (code "53") (name "SCK") (class "Default")
      (node (ref "U$5") (pin "D13") (pinfunction "D13_D13") (pintype "bidirectional"))
      (node (ref "U$6") (pin "41") (pinfunction "SCKI_41") (pintype "bidirectional"))
    )
    (net (code "54") (name "SS") (class "Default")
      (node (ref "U$5") (pin "D10") (pinfunction "*D10_D10") (pintype "bidirectional"))
      (node (ref "U$6") (pin "44") (pinfunction "CSBI_44") (pintype "bidirectional"))
    )
    (net (code "55") (name "VREG") (class "Default")
      (node (ref "A1") (pin "1") (pinfunction "1_1") (pintype "passive"))
      (node (ref "A2") (pin "1") (pinfunction "1_1") (pintype "passive"))
      (node (ref "A3") (pin "1") (pinfunction "1_1") (pintype "passive"))
      (node (ref "A4") (pin "1") (pinfunction "1_1") (pintype "passive"))
      (node (ref "C7") (pin "1") (pinfunction "1_1") (pintype "passive"))
      (node (ref "R12") (pin "2") (pinfunction "2_2") (pintype "passive"))
      (node (ref "TOS") (pin "1") (pinfunction "1_1") (pintype "passive"))
      (node (ref "U$6") (pin "31") (pinfunction "VREG_31") (pintype "bidirectional"))
    )
    (net (code "56") (name "unconnected-(U$5-*D3-PadD3)") (class "Default")
      (node (ref "U$5") (pin "D3") (pinfunction "*D3_D3") (pintype "bidirectional"))
    )
    (net (code "57") (name "unconnected-(U$5-*D5-PadD5)") (class "Default")
      (node (ref "U$5") (pin "D5") (pinfunction "*D5_D5") (pintype "bidirectional"))
    )
    (net (code "58") (name "unconnected-(U$5-Pad3.3V)") (class "Default")
      (node (ref "U$5") (pin "3.3V") (pinfunction "3.3V_3.3V") (pintype "bidirectional"))
    )
    (net (code "59") (name "unconnected-(U$5-PadA0)") (class "Default")
      (node (ref "U$5") (pin "A0") (pinfunction "A0_A0") (pintype "bidirectional"))
    )
    (net (code "60") (name "unconnected-(U$5-PadA1)") (class "Default")
      (node (ref "U$5") (pin "A1") (pinfunction "A1_A1") (pintype "bidirectional"))
    )
    (net (code "61") (name "unconnected-(U$5-PadA2)") (class "Default")
      (node (ref "U$5") (pin "A2") (pinfunction "A2_A2") (pintype "bidirectional"))
    )
    (net (code "62") (name "unconnected-(U$5-PadA3)") (class "Default")
      (node (ref "U$5") (pin "A3") (pinfunction "A3_A3") (pintype "bidirectional"))
    )
    (net (code "63") (name "unconnected-(U$5-PadA4)") (class "Default")
      (node (ref "U$5") (pin "A4") (pinfunction "A4_A4") (pintype "bidirectional"))
    )
    (net (code "64") (name "unconnected-(U$5-PadA5)") (class "Default")
      (node (ref "U$5") (pin "A5") (pinfunction "A5_A5") (pintype "bidirectional"))
    )
    (net (code "65") (name "unconnected-(U$5-PadAREF)") (class "Default")
      (node (ref "U$5") (pin "AREF") (pinfunction "AREF_AREF") (pintype "bidirectional"))
    )
    (net (code "66") (name "unconnected-(U$5-PadD2)") (class "Default")
      (node (ref "U$5") (pin "D2") (pinfunction "D2_D2") (pintype "bidirectional"))
    )
    (net (code "67") (name "unconnected-(U$5-PadD4)") (class "Default")
      (node (ref "U$5") (pin "D4") (pinfunction "D4_D4") (pintype "bidirectional"))
    )
    (net (code "68") (name "unconnected-(U$5-PadIOREF)") (class "Default")
      (node (ref "U$5") (pin "IOREF") (pinfunction "IOREF_IOREF") (pintype "bidirectional"))
    )
    (net (code "69") (name "unconnected-(U$5-PadRES)") (class "Default")
      (node (ref "U$5") (pin "RES") (pinfunction "RES_RES") (pintype "bidirectional"))
    )
    (net (code "70") (name "unconnected-(U$5-PadRX)") (class "Default")
      (node (ref "U$5") (pin "RX") (pinfunction "RX_RX") (pintype "bidirectional"))
    )
    (net (code "71") (name "unconnected-(U$5-PadTX)") (class "Default")
      (node (ref "U$5") (pin "TX") (pinfunction "TX_TX") (pintype "bidirectional"))
    )
    (net (code "72") (name "unconnected-(U$6-NC-Pad27)") (class "Default")
      (node (ref "U$6") (pin "27") (pinfunction "NC_27") (pintype "bidirectional"))
    )
    (net (code "73") (name "unconnected-(U$6-NC1-Pad33)") (class "Default")
      (node (ref "U$6") (pin "33") (pinfunction "NC1_33") (pintype "bidirectional"))
    )
    (net (code "74") (name "unconnected-(U$6-S4-Pad19)") (class "Default")
      (node (ref "U$6") (pin "19") (pinfunction "S4_19") (pintype "bidirectional"))
    )
    (net (code "75") (name "unconnected-(U$6-S5-Pad17)") (class "Default")
      (node (ref "U$6") (pin "17") (pinfunction "S5_17") (pintype "bidirectional"))
    )
    (net (code "76") (name "unconnected-(U$6-S6-Pad15)") (class "Default")
      (node (ref "U$6") (pin "15") (pinfunction "S6_15") (pintype "bidirectional"))
    )
    (net (code "77") (name "unconnected-(U$6-S7-Pad13)") (class "Default")
      (node (ref "U$6") (pin "13") (pinfunction "S7_13") (pintype "bidirectional"))
    )
    (net (code "78") (name "unconnected-(U$6-S8-Pad11)") (class "Default")
      (node (ref "U$6") (pin "11") (pinfunction "S8_11") (pintype "bidirectional"))
    )
    (net (code "79") (name "unconnected-(U$6-S9-Pad9)") (class "Default")
      (node (ref "U$6") (pin "9") (pinfunction "S9_9") (pintype "bidirectional"))
    )
    (net (code "80") (name "unconnected-(U$6-S10-Pad7)") (class "Default")
      (node (ref "U$6") (pin "7") (pinfunction "S10_7") (pintype "bidirectional"))
    )
    (net (code "81") (name "unconnected-(U$6-S11-Pad5)") (class "Default")
      (node (ref "U$6") (pin "5") (pinfunction "S11_5") (pintype "bidirectional"))
    )
    (net (code "82") (name "unconnected-(U$6-S12-Pad3)") (class "Default")
      (node (ref "U$6") (pin "3") (pinfunction "S12_3") (pintype "bidirectional"))
    )
    (net (code "83") (name "unconnected-(U$6-VTEMP2-Pad29)") (class "Default")
      (node (ref "U$6") (pin "29") (pinfunction "VTEMP2_29") (pintype "bidirectional"))
    )
  )
)
